# Down_Linker_ver2_0_0.net
KiCad netlist of a schematic drawn in EAGLE
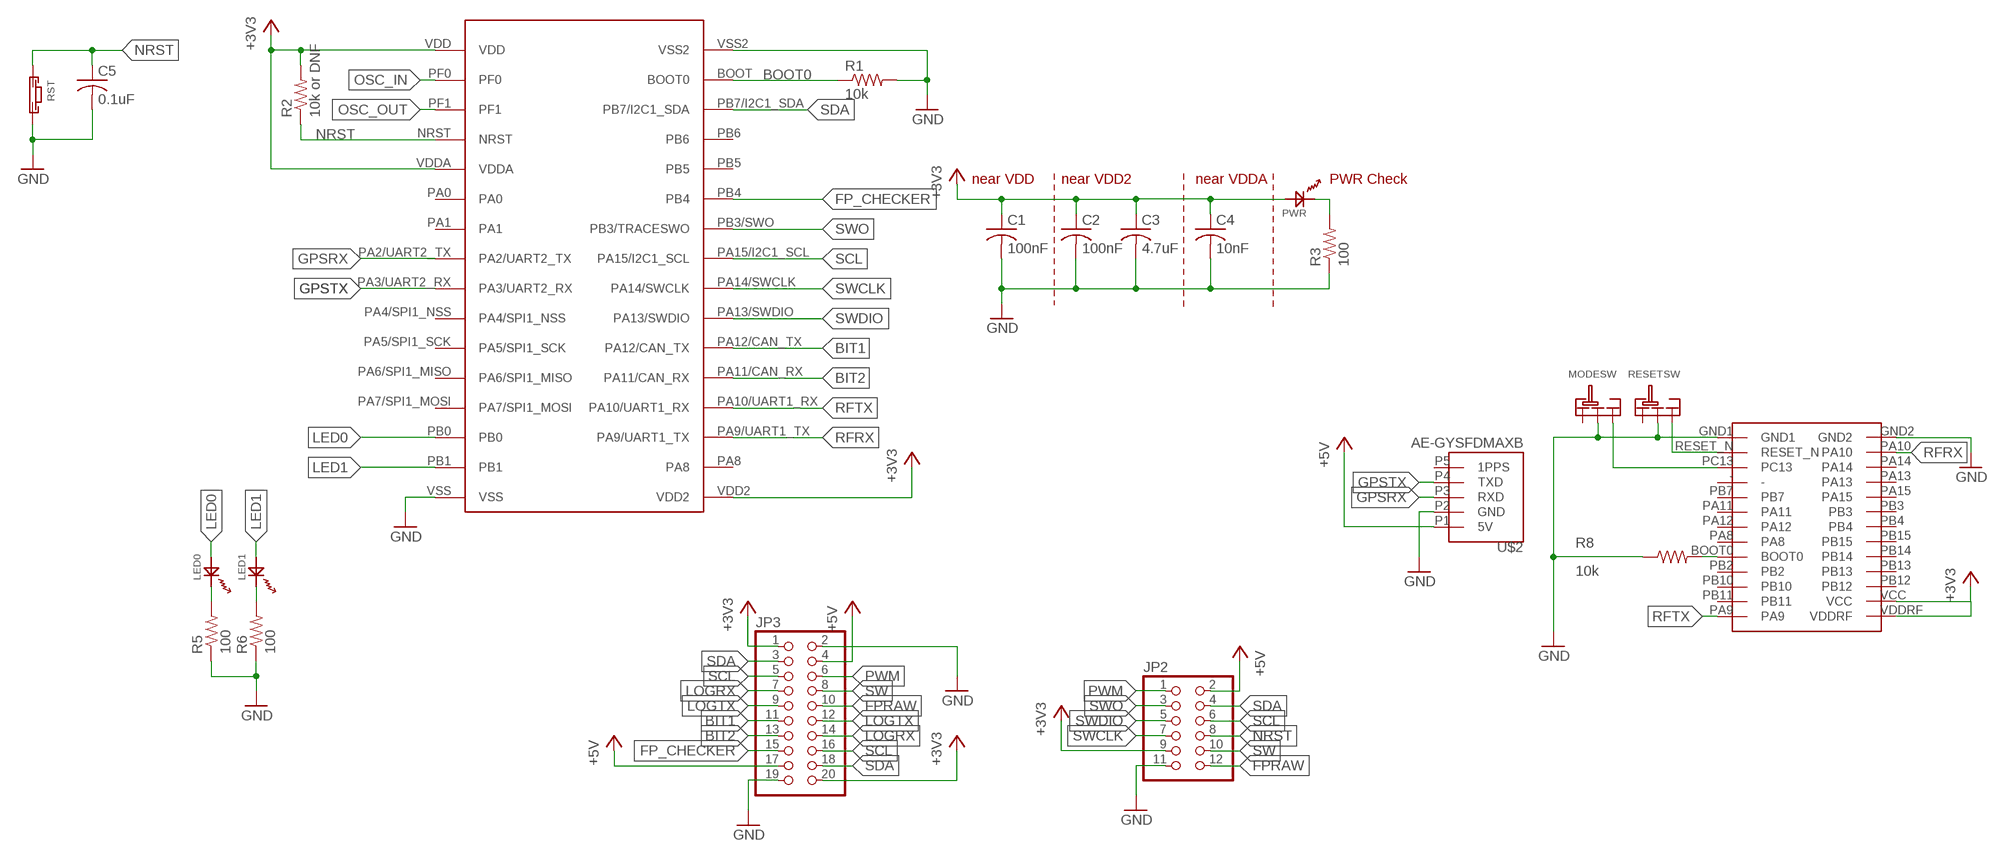
[diagram p0: schematic, sheet 1]

(export (version "E")
  (design (tool "Eeschema 10.0.6"))
  (components
    (comp (ref "C1")
      (value "100nF")
      (footprint "eagle-import:C1608")
      (libsource (lib "eagle-import") (part "C-USC1608"))
    )
    (comp (ref "C2")
      (value "100nF")
      (footprint "eagle-import:C1608")
      (libsource (lib "eagle-import") (part "C-USC1608"))
    )
    (comp (ref "C3")
      (value "4.7uF")
      (footprint "eagle-import:C1608")
      (libsource (lib "eagle-import") (part "C-USC1608"))
    )
    (comp (ref "C4")
      (value "10nF")
      (footprint "eagle-import:C1608")
      (libsource (lib "eagle-import") (part "C-USC1608"))
    )
    (comp (ref "C5")
      (value "0.1uF")
      (footprint "eagle-import:C1608")
      (libsource (lib "eagle-import") (part "C-USC1608"))
    )
    (comp (ref "JP2")
      (value "PINHD-2X6/90")
      (footprint "eagle-import:2X06_90")
      (libsource (lib "eagle-import") (part "PINHD-2X6/90"))
    )
    (comp (ref "JP3")
      (value "PINHD-2X10/90")
      (footprint "eagle-import:2X10_90")
      (libsource (lib "eagle-import") (part "PINHD-2X10/90"))
    )
    (comp (ref "LED0")
      (value "OSXX1608C1A")
      (footprint "eagle-import:OSXX1608C1A")
      (libsource (lib "eagle-import") (part "OSXX1608C1A"))
    )
    (comp (ref "LED1")
      (value "OSXX1608C1A")
      (footprint "eagle-import:OSXX1608C1A")
      (libsource (lib "eagle-import") (part "OSXX1608C1A"))
    )
    (comp (ref "MODESW")
      (value "SRIDE_SWITCH")
      (footprint "eagle-import:SRIDE_SWITCH")
      (libsource (lib "eagle-import") (part "SRIDE_SWITCH"))
    )
    (comp (ref "PWR")
      (value "OSXX1608C1A")
      (footprint "eagle-import:OSXX1608C1A")
      (libsource (lib "eagle-import") (part "OSXX1608C1A"))
    )
    (comp (ref "R1")
      (value "10k")
      (footprint "eagle-import:R0603")
      (libsource (lib "eagle-import") (part "R-US_R0603"))
    )
    (comp (ref "R2")
      (value "10k or DNF")
      (footprint "eagle-import:R0603")
      (libsource (lib "eagle-import") (part "R-US_R0603"))
    )
    (comp (ref "R3")
      (value "100")
      (footprint "eagle-import:R0603")
      (libsource (lib "eagle-import") (part "R-US_R0603"))
    )
    (comp (ref "R5")
      (value "100")
      (footprint "eagle-import:R0603")
      (libsource (lib "eagle-import") (part "R-US_R0603"))
    )
    (comp (ref "R6")
      (value "100")
      (footprint "eagle-import:R0603")
      (libsource (lib "eagle-import") (part "R-US_R0603"))
    )
    (comp (ref "R8")
      (value "10k")
      (footprint "eagle-import:R0603")
      (libsource (lib "eagle-import") (part "R-US_R0603"))
    )
    (comp (ref "RESETSW")
      (value "SRIDE_SWITCH")
      (footprint "eagle-import:SRIDE_SWITCH")
      (libsource (lib "eagle-import") (part "SRIDE_SWITCH"))
    )
    (comp (ref "RST")
      (value "TVAF06-A020B-R")
      (footprint "eagle-import:TVAF06-A020B-R")
      (libsource (lib "eagle-import") (part "TVAF06-A020B-R"))
    )
    (comp (ref "U$1")
      (value "STM32F303K8")
      (footprint "eagle-import:STM32F303K8")
      (libsource (lib "eagle-import") (part "STM32F303K8"))
    )
    (comp (ref "U$2")
      (value "AE-GYSFDMAXB")
      (footprint "eagle-import:AE-GYSFDMAXB")
      (libsource (lib "eagle-import") (part "AE-GYSFDMAXB"))
    )
    (comp (ref "U$3")
      (value "RM-92A")
      (footprint "eagle-import:RM-92A")
      (libsource (lib "eagle-import") (part "RM-92A"))
    )
  )
  (nets
    (net (code "1") (name "+3V3") (class "Default")
      (node (ref "C1") (pin "1") (pinfunction "1_1") (pintype "passive"))
      (node (ref "C2") (pin "1") (pinfunction "1_1") (pintype "passive"))
      (node (ref "C3") (pin "1") (pinfunction "1_1") (pintype "passive"))
      (node (ref "C4") (pin "1") (pinfunction "1_1") (pintype "passive"))
      (node (ref "JP2") (pin "9") (pinfunction "9_9") (pintype "passive"))
      (node (ref "JP3") (pin "1") (pinfunction "1_1") (pintype "passive"))
      (node (ref "JP3") (pin "20") (pinfunction "20_20") (pintype "passive"))
      (node (ref "PWR") (pin "AN") (pinfunction "AN_AN") (pintype "bidirectional"))
      (node (ref "R2") (pin "2") (pinfunction "2_2") (pintype "passive"))
      (node (ref "U$1") (pin "VDD") (pinfunction "VDD_VDD") (pintype "power_in"))
      (node (ref "U$1") (pin "VDD2") (pinfunction "VDD2_VDD2") (pintype "power_in"))
      (node (ref "U$1") (pin "VDDA") (pinfunction "VDDA_VDDA") (pintype "power_in"))
      (node (ref "U$3") (pin "VCC") (pinfunction "VCC_VCC") (pintype "bidirectional"))
      (node (ref "U$3") (pin "VDDRF") (pinfunction "VDDRF_VDDRF") (pintype "bidirectional"))
    )
    (net (code "2") (name "+5V") (class "Default")
      (node (ref "JP2") (pin "2") (pinfunction "2_2") (pintype "passive"))
      (node (ref "JP3") (pin "17") (pinfunction "17_17") (pintype "passive"))
      (node (ref "JP3") (pin "4") (pinfunction "4_4") (pintype "passive"))
      (node (ref "U$2") (pin "P1") (pinfunction "5V_P1") (pintype "bidirectional"))
    )
    (net (code "3") (name "/BOOT0") (class "Default")
      (node (ref "R1") (pin "1") (pinfunction "1_1") (pintype "passive"))
      (node (ref "U$1") (pin "BOOT") (pinfunction "BOOT0_BOOT") (pintype "bidirectional"))
    )
    (net (code "4") (name "BIT1") (class "Default")
      (node (ref "JP3") (pin "11") (pinfunction "11_11") (pintype "passive"))
      (node (ref "U$1") (pin "PA12/CAN_TX") (pinfunction "PA12/CAN_TX_PA12/CAN_TX") (pintype "bidirectional"))
    )
    (net (code "5") (name "BIT2") (class "Default")
      (node (ref "JP3") (pin "13") (pinfunction "13_13") (pintype "passive"))
      (node (ref "U$1") (pin "PA11/CAN_RX") (pinfunction "PA11/CAN_RX_PA11/CAN_RX") (pintype "bidirectional"))
    )
    (net (code "6") (name "FPRAW") (class "Default")
      (node (ref "JP2") (pin "12") (pinfunction "12_12") (pintype "passive"))
      (node (ref "JP3") (pin "10") (pinfunction "10_10") (pintype "passive"))
    )
    (net (code "7") (name "FP_CHECKER") (class "Default")
      (node (ref "JP3") (pin "15") (pinfunction "15_15") (pintype "passive"))
      (node (ref "U$1") (pin "PB4") (pinfunction "PB4_PB4") (pintype "bidirectional"))
    )
    (net (code "8") (name "GND") (class "Default")
      (node (ref "C1") (pin "2") (pinfunction "2_2") (pintype "passive"))
      (node (ref "C2") (pin "2") (pinfunction "2_2") (pintype "passive"))
      (node (ref "C3") (pin "2") (pinfunction "2_2") (pintype "passive"))
      (node (ref "C4") (pin "2") (pinfunction "2_2") (pintype "passive"))
      (node (ref "C5") (pin "2") (pinfunction "2_2") (pintype "passive"))
      (node (ref "JP2") (pin "11") (pinfunction "11_11") (pintype "passive"))
      (node (ref "JP3") (pin "19") (pinfunction "19_19") (pintype "passive"))
      (node (ref "JP3") (pin "2") (pinfunction "2_2") (pintype "passive"))
      (node (ref "MODESW") (pin "LR") (pinfunction "LR_LR") (pintype "bidirectional"))
      (node (ref "R1") (pin "2") (pinfunction "2_2") (pintype "passive"))
      (node (ref "R3") (pin "1") (pinfunction "1_1") (pintype "passive"))
      (node (ref "R5") (pin "1") (pinfunction "1_1") (pintype "passive"))
      (node (ref "R6") (pin "1") (pinfunction "1_1") (pintype "passive"))
      (node (ref "R8") (pin "1") (pinfunction "1_1") (pintype "passive"))
      (node (ref "RESETSW") (pin "LR") (pinfunction "LR_LR") (pintype "bidirectional"))
      (node (ref "RST") (pin "P$2") (pinfunction "P$2_P$2") (pintype "bidirectional"))
      (node (ref "U$1") (pin "VSS") (pinfunction "VSS_VSS") (pintype "power_in"))
      (node (ref "U$1") (pin "VSS2") (pinfunction "VSS2_VSS2") (pintype "power_in"))
      (node (ref "U$2") (pin "P2") (pinfunction "GND_P2") (pintype "bidirectional"))
      (node (ref "U$3") (pin "GND1") (pinfunction "GND1_GND1") (pintype "bidirectional"))
      (node (ref "U$3") (pin "GND2") (pinfunction "GND2_GND2") (pintype "bidirectional"))
    )
    (net (code "9") (name "GPSRX") (class "Default")
      (node (ref "U$1") (pin "PA2/UART2_TX") (pinfunction "PA2/UART2_TX_PA2/UART2_TX") (pintype "bidirectional"))
      (node (ref "U$2") (pin "P3") (pinfunction "RXD_P3") (pintype "bidirectional"))
    )
    (net (code "10") (name "GPSTX") (class "Default")
      (node (ref "U$1") (pin "PA3/UART2_RX") (pinfunction "PA3/UART2_RX_PA3/UART2_RX") (pintype "bidirectional"))
      (node (ref "U$2") (pin "P4") (pinfunction "TXD_P4") (pintype "bidirectional"))
    )
    (net (code "11") (name "LED0") (class "Default")
      (node (ref "LED0") (pin "AN") (pinfunction "AN_AN") (pintype "bidirectional"))
      (node (ref "U$1") (pin "PB0") (pinfunction "PB0_PB0") (pintype "bidirectional"))
    )
    (net (code "12") (name "LED1") (class "Default")
      (node (ref "LED1") (pin "AN") (pinfunction "AN_AN") (pintype "bidirectional"))
      (node (ref "U$1") (pin "PB1") (pinfunction "PB1_PB1") (pintype "bidirectional"))
    )
    (net (code "13") (name "LOGRX") (class "Default")
      (node (ref "JP3") (pin "14") (pinfunction "14_14") (pintype "passive"))
      (node (ref "JP3") (pin "7") (pinfunction "7_7") (pintype "passive"))
    )
    (net (code "14") (name "LOGTX") (class "Default")
      (node (ref "JP3") (pin "12") (pinfunction "12_12") (pintype "passive"))
      (node (ref "JP3") (pin "9") (pinfunction "9_9") (pintype "passive"))
    )
    (net (code "15") (name "NRST") (class "Default")
      (node (ref "C5") (pin "1") (pinfunction "1_1") (pintype "passive"))
      (node (ref "JP2") (pin "8") (pinfunction "8_8") (pintype "passive"))
      (node (ref "R2") (pin "1") (pinfunction "1_1") (pintype "passive"))
      (node (ref "RST") (pin "P$1") (pinfunction "P$1_P$1") (pintype "bidirectional"))
      (node (ref "U$1") (pin "NRST") (pinfunction "NRST_NRST") (pintype "bidirectional"))
    )
    (net (code "16") (name "Net-(LED0-PadCT)") (class "Default")
      (node (ref "LED0") (pin "CT") (pinfunction "CT_CT") (pintype "bidirectional"))
      (node (ref "R5") (pin "2") (pinfunction "2_2") (pintype "passive"))
    )
    (net (code "17") (name "Net-(LED1-PadCT)") (class "Default")
      (node (ref "LED1") (pin "CT") (pinfunction "CT_CT") (pintype "bidirectional"))
      (node (ref "R6") (pin "2") (pinfunction "2_2") (pintype "passive"))
    )
    (net (code "18") (name "Net-(MODESW-PadR)") (class "Default")
      (node (ref "MODESW") (pin "R") (pinfunction "R_R") (pintype "bidirectional"))
      (node (ref "U$3") (pin "PC13") (pinfunction "PC13_PC13") (pintype "bidirectional"))
    )
    (net (code "19") (name "Net-(PWR-PadCT)") (class "Default")
      (node (ref "PWR") (pin "CT") (pinfunction "CT_CT") (pintype "bidirectional"))
      (node (ref "R3") (pin "2") (pinfunction "2_2") (pintype "passive"))
    )
    (net (code "20") (name "Net-(R8-Pad2)") (class "Default")
      (node (ref "R8") (pin "2") (pinfunction "2_2") (pintype "passive"))
      (node (ref "U$3") (pin "BOOT0") (pinfunction "BOOT0_BOOT0") (pintype "bidirectional"))
    )
    (net (code "21") (name "Net-(RESETSW-PadR)") (class "Default")
      (node (ref "RESETSW") (pin "R") (pinfunction "R_R") (pintype "bidirectional"))
      (node (ref "U$3") (pin "RESET_N") (pinfunction "RESET_N_RESET_N") (pintype "bidirectional"))
    )
    (net (code "22") (name "OSC_IN") (class "Default")
      (node (ref "U$1") (pin "PF0") (pinfunction "PF0_PF0") (pintype "bidirectional"))
    )
    (net (code "23") (name "OSC_OUT") (class "Default")
      (node (ref "U$1") (pin "PF1") (pinfunction "PF1_PF1") (pintype "bidirectional"))
    )
    (net (code "24") (name "PWM") (class "Default")
      (node (ref "JP2") (pin "1") (pinfunction "1_1") (pintype "passive"))
      (node (ref "JP3") (pin "6") (pinfunction "6_6") (pintype "passive"))
    )
    (net (code "25") (name "RFRX") (class "Default")
      (node (ref "U$1") (pin "PA9/UART1_TX") (pinfunction "PA9/UART1_TX_PA9/UART1_TX") (pintype "bidirectional"))
      (node (ref "U$3") (pin "PA10") (pinfunction "PA10_PA10") (pintype "bidirectional"))
    )
    (net (code "26") (name "RFTX") (class "Default")
      (node (ref "U$1") (pin "PA10/UART1_RX") (pinfunction "PA10/UART1_RX_PA10/UART1_RX") (pintype "bidirectional"))
      (node (ref "U$3") (pin "PA9") (pinfunction "PA9_PA9") (pintype "bidirectional"))
    )
    (net (code "27") (name "SCL") (class "Default")
      (node (ref "JP2") (pin "6") (pinfunction "6_6") (pintype "passive"))
      (node (ref "JP3") (pin "16") (pinfunction "16_16") (pintype "passive"))
      (node (ref "JP3") (pin "5") (pinfunction "5_5") (pintype "passive"))
      (node (ref "U$1") (pin "PA15/I2C1_SCL") (pinfunction "PA15/I2C1_SCL_PA15/I2C1_SCL") (pintype "bidirectional"))
    )
    (net (code "28") (name "SDA") (class "Default")
      (node (ref "JP2") (pin "4") (pinfunction "4_4") (pintype "passive"))
      (node (ref "JP3") (pin "18") (pinfunction "18_18") (pintype "passive"))
      (node (ref "JP3") (pin "3") (pinfunction "3_3") (pintype "passive"))
      (node (ref "U$1") (pin "PB7/I2C1_SDA") (pinfunction "PB7/I2C1_SDA_PB7/I2C1_SDA") (pintype "bidirectional"))
    )
    (net (code "29") (name "SW") (class "Default")
      (node (ref "JP2") (pin "10") (pinfunction "10_10") (pintype "passive"))
      (node (ref "JP3") (pin "8") (pinfunction "8_8") (pintype "passive"))
    )
    (net (code "30") (name "SWCLK") (class "Default")
      (node (ref "JP2") (pin "7") (pinfunction "7_7") (pintype "passive"))
      (node (ref "U$1") (pin "PA14/SWCLK") (pinfunction "PA14/SWCLK_PA14/SWCLK") (pintype "bidirectional"))
    )
    (net (code "31") (name "SWDIO") (class "Default")
      (node (ref "JP2") (pin "5") (pinfunction "5_5") (pintype "passive"))
      (node (ref "U$1") (pin "PA13/SWDIO") (pinfunction "PA13/SWDIO_PA13/SWDIO") (pintype "bidirectional"))
    )
    (net (code "32") (name "SWO") (class "Default")
      (node (ref "JP2") (pin "3") (pinfunction "3_3") (pintype "passive"))
      (node (ref "U$1") (pin "PB3/SWO") (pinfunction "PB3/TRACESWO_PB3/SWO") (pintype "bidirectional"))
    )
    (net (code "33") (name "unconnected-(MODESW-PadL)") (class "Default")
      (node (ref "MODESW") (pin "L") (pinfunction "L_L") (pintype "bidirectional"))
    )
    (net (code "34") (name "unconnected-(RESETSW-PadL)") (class "Default")
      (node (ref "RESETSW") (pin "L") (pinfunction "L_L") (pintype "bidirectional"))
    )
    (net (code "35") (name "unconnected-(U$1-PadPA0)") (class "Default")
      (node (ref "U$1") (pin "PA0") (pinfunction "PA0_PA0") (pintype "bidirectional"))
    )
    (net (code "36") (name "unconnected-(U$1-PadPA1)") (class "Default")
      (node (ref "U$1") (pin "PA1") (pinfunction "PA1_PA1") (pintype "bidirectional"))
    )
    (net (code "37") (name "unconnected-(U$1-PadPA4{slash}SPI1_NSS)") (class "Default")
      (node (ref "U$1") (pin "PA4/SPI1_NSS") (pinfunction "PA4/SPI1_NSS_PA4/SPI1_NSS") (pintype "bidirectional"))
    )
    (net (code "38") (name "unconnected-(U$1-PadPA5{slash}SPI1_SCK)") (class "Default")
      (node (ref "U$1") (pin "PA5/SPI1_SCK") (pinfunction "PA5/SPI1_SCK_PA5/SPI1_SCK") (pintype "bidirectional"))
    )
    (net (code "39") (name "unconnected-(U$1-PadPA6{slash}SPI1_MISO)") (class "Default")
      (node (ref "U$1") (pin "PA6/SPI1_MISO") (pinfunction "PA6/SPI1_MISO_PA6/SPI1_MISO") (pintype "bidirectional"))
    )
    (net (code "40") (name "unconnected-(U$1-PadPA7{slash}SPI1_MOSI)") (class "Default")
      (node (ref "U$1") (pin "PA7/SPI1_MOSI") (pinfunction "PA7/SPI1_MOSI_PA7/SPI1_MOSI") (pintype "bidirectional"))
    )
    (net (code "41") (name "unconnected-(U$1-PadPA8)") (class "Default")
      (node (ref "U$1") (pin "PA8") (pinfunction "PA8_PA8") (pintype "bidirectional"))
    )
    (net (code "42") (name "unconnected-(U$1-PadPB5)") (class "Default")
      (node (ref "U$1") (pin "PB5") (pinfunction "PB5_PB5") (pintype "bidirectional"))
    )
    (net (code "43") (name "unconnected-(U$1-PadPB6)") (class "Default")
      (node (ref "U$1") (pin "PB6") (pinfunction "PB6_PB6") (pintype "bidirectional"))
    )
    (net (code "44") (name "unconnected-(U$2-1PPS-PadP5)") (class "Default")
      (node (ref "U$2") (pin "P5") (pinfunction "1PPS_P5") (pintype "bidirectional"))
    )
    (net (code "45") (name "unconnected-(U$3-Pad-)") (class "Default")
      (node (ref "U$3") (pin "-") (pinfunction "-_-") (pintype "bidirectional"))
    )
    (net (code "46") (name "unconnected-(U$3-PadPA8)") (class "Default")
      (node (ref "U$3") (pin "PA8") (pinfunction "PA8_PA8") (pintype "bidirectional"))
    )
    (net (code "47") (name "unconnected-(U$3-PadPA11)") (class "Default")
      (node (ref "U$3") (pin "PA11") (pinfunction "PA11_PA11") (pintype "bidirectional"))
    )
    (net (code "48") (name "unconnected-(U$3-PadPA12)") (class "Default")
      (node (ref "U$3") (pin "PA12") (pinfunction "PA12_PA12") (pintype "bidirectional"))
    )
    (net (code "49") (name "unconnected-(U$3-PadPA13)") (class "Default")
      (node (ref "U$3") (pin "PA13") (pinfunction "PA13_PA13") (pintype "bidirectional"))
    )
    (net (code "50") (name "unconnected-(U$3-PadPA14)") (class "Default")
      (node (ref "U$3") (pin "PA14") (pinfunction "PA14_PA14") (pintype "bidirectional"))
    )
    (net (code "51") (name "unconnected-(U$3-PadPA15)") (class "Default")
      (node (ref "U$3") (pin "PA15") (pinfunction "PA15_PA15") (pintype "bidirectional"))
    )
    (net (code "52") (name "unconnected-(U$3-PadPB2)") (class "Default")
      (node (ref "U$3") (pin "PB2") (pinfunction "PB2_PB2") (pintype "bidirectional"))
    )
    (net (code "53") (name "unconnected-(U$3-PadPB3)") (class "Default")
      (node (ref "U$3") (pin "PB3") (pinfunction "PB3_PB3") (pintype "bidirectional"))
    )
    (net (code "54") (name "unconnected-(U$3-PadPB4)") (class "Default")
      (node (ref "U$3") (pin "PB4") (pinfunction "PB4_PB4") (pintype "bidirectional"))
    )
    (net (code "55") (name "unconnected-(U$3-PadPB7)") (class "Default")
      (node (ref "U$3") (pin "PB7") (pinfunction "PB7_PB7") (pintype "bidirectional"))
    )
    (net (code "56") (name "unconnected-(U$3-PadPB10)") (class "Default")
      (node (ref "U$3") (pin "PB10") (pinfunction "PB10_PB10") (pintype "bidirectional"))
    )
    (net (code "57") (name "unconnected-(U$3-PadPB11)") (class "Default")
      (node (ref "U$3") (pin "PB11") (pinfunction "PB11_PB11") (pintype "bidirectional"))
    )
    (net (code "58") (name "unconnected-(U$3-PadPB12)") (class "Default")
      (node (ref "U$3") (pin "PB12") (pinfunction "PB12_PB12") (pintype "bidirectional"))
    )
    (net (code "59") (name "unconnected-(U$3-PadPB13)") (class "Default")
      (node (ref "U$3") (pin "PB13") (pinfunction "PB13_PB13") (pintype "bidirectional"))
    )
    (net (code "60") (name "unconnected-(U$3-PadPB14)") (class "Default")
      (node (ref "U$3") (pin "PB14") (pinfunction "PB14_PB14") (pintype "bidirectional"))
    )
    (net (code "61") (name "unconnected-(U$3-PadPB15)") (class "Default")
      (node (ref "U$3") (pin "PB15") (pinfunction "PB15_PB15") (pintype "bidirectional"))
    )
  )
)
